# SparkFun_MicroMod_DA16200_Function.net
KiCad netlist of a schematic drawn in EAGLE
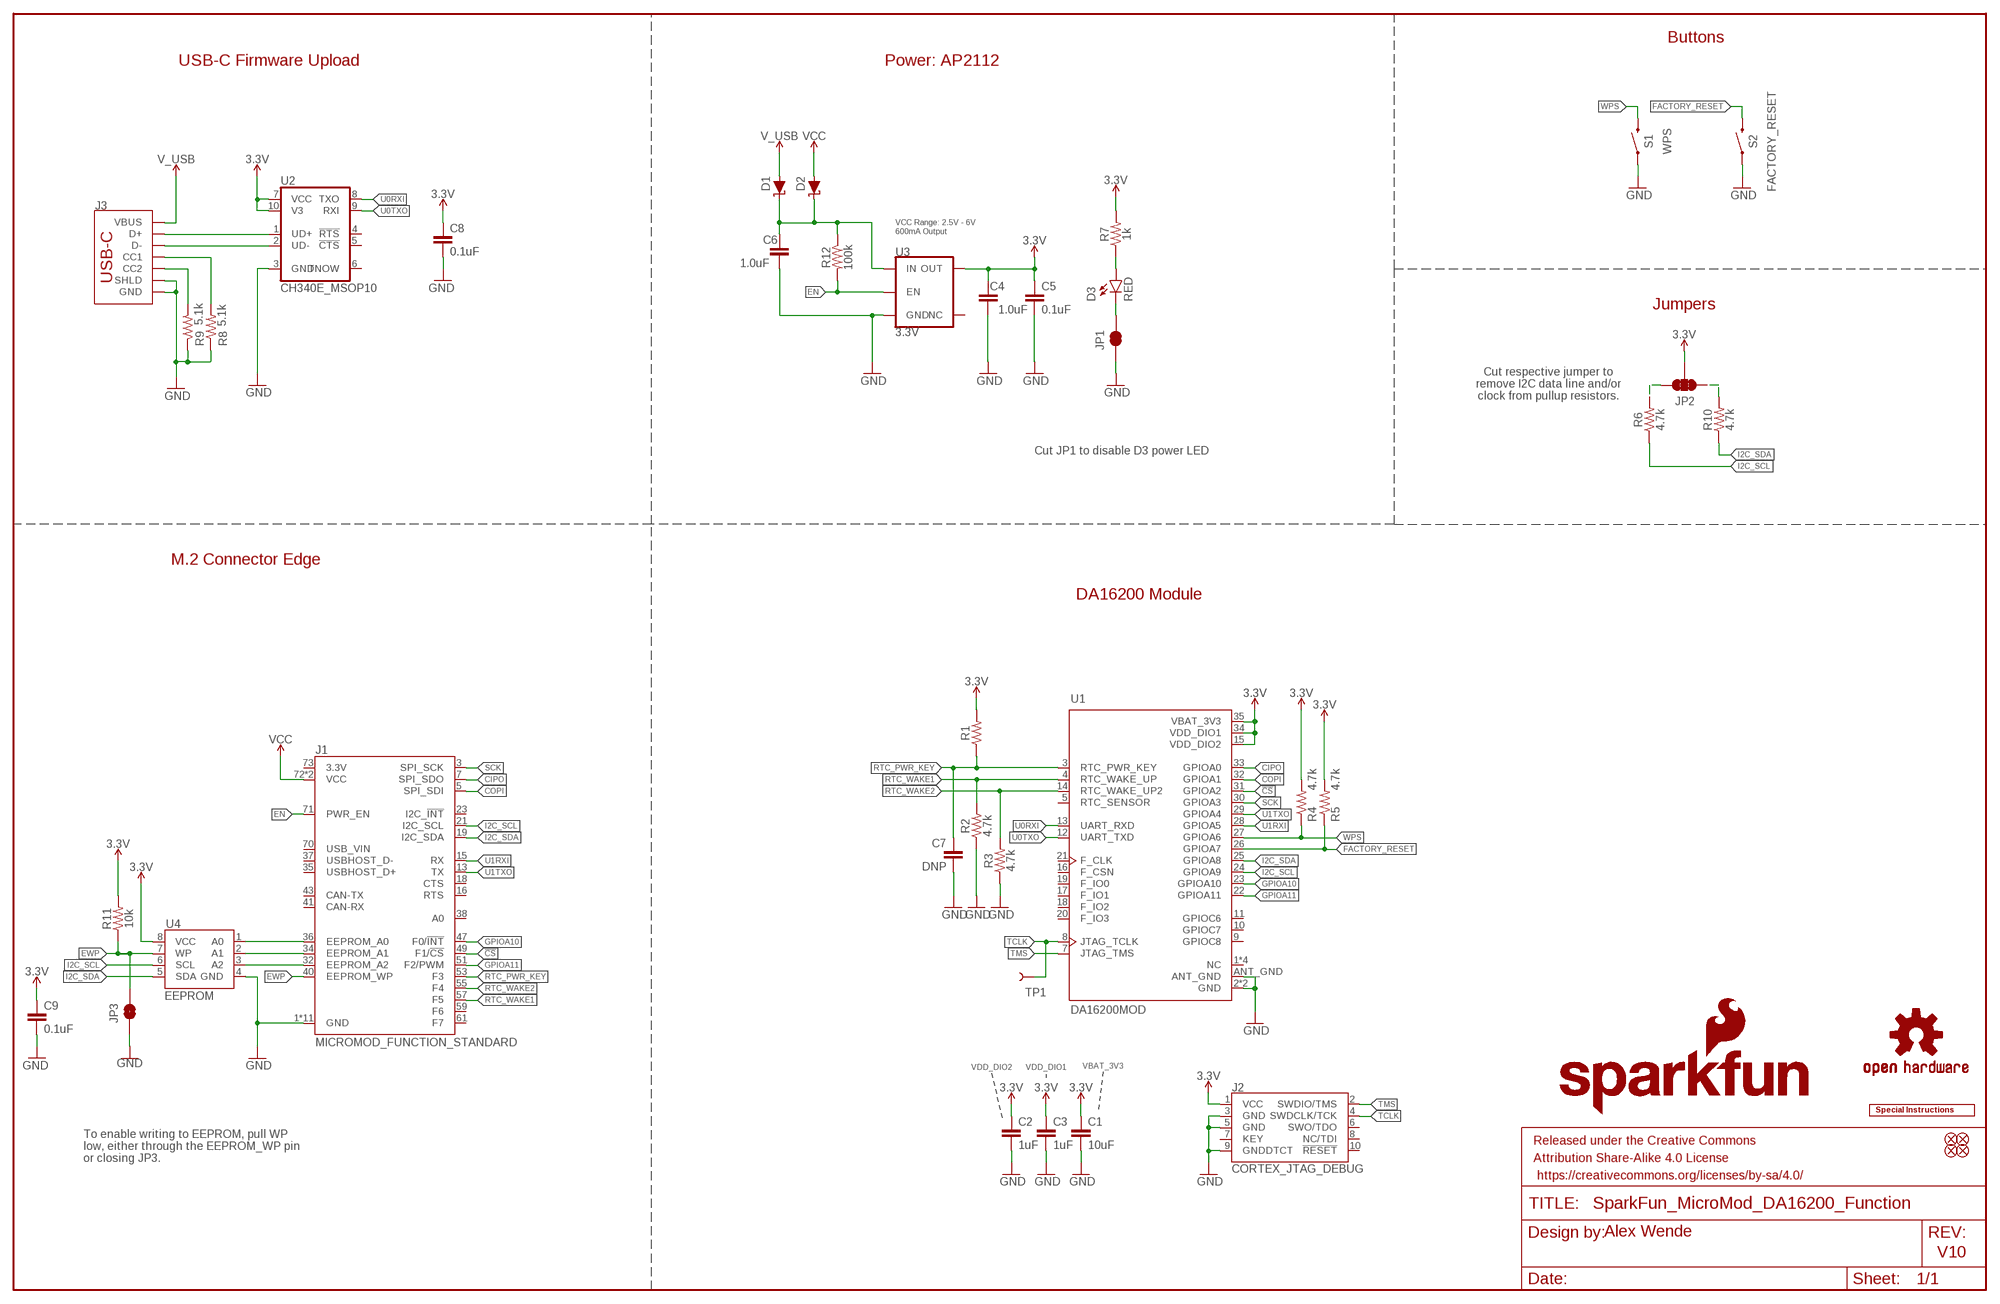
[diagram p0: schematic, sheet 1]

(export (version "E")
  (design (tool "Eeschema 10.0.6"))
  (components
    (comp (ref "C1")
      (value "10uF")
      (footprint "eagle-import:0603")
      (libsource (lib "eagle-import") (part "10UF-0603-6.3V-20%"))
    )
    (comp (ref "C2")
      (value "1uF")
      (footprint "eagle-import:0603")
      (libsource (lib "eagle-import") (part "1.0UF-0603-16V-10%"))
    )
    (comp (ref "C3")
      (value "1uF")
      (footprint "eagle-import:0603")
      (libsource (lib "eagle-import") (part "1.0UF-0603-16V-10%"))
    )
    (comp (ref "C4")
      (value "1.0uF")
      (footprint "eagle-import:0603")
      (libsource (lib "eagle-import") (part "1.0UF-0603-16V-10%"))
    )
    (comp (ref "C5")
      (value "0.1uF")
      (footprint "eagle-import:0603")
      (libsource (lib "eagle-import") (part "0.1UF-0603-25V-(+80/-20%)"))
    )
    (comp (ref "C6")
      (value "1.0uF")
      (footprint "eagle-import:0603")
      (libsource (lib "eagle-import") (part "1.0UF-0603-16V-10%"))
    )
    (comp (ref "C7")
      (value "DNP")
      (footprint "eagle-import:0603")
      (libsource (lib "eagle-import") (part "CAP-0603"))
    )
    (comp (ref "C8")
      (value "0.1uF")
      (footprint "eagle-import:0603")
      (libsource (lib "eagle-import") (part "0.1UF-0603-25V-(+80/-20%)"))
    )
    (comp (ref "C9")
      (value "0.1uF")
      (footprint "eagle-import:0603")
      (libsource (lib "eagle-import") (part "0.1UF-0603-25V-(+80/-20%)"))
    )
    (comp (ref "D1")
      (value "DIODE-SCHOTTKY-BAT60A")
      (footprint "eagle-import:SOD-323")
      (libsource (lib "eagle-import") (part "DIODE-SCHOTTKY-BAT60A"))
    )
    (comp (ref "D2")
      (value "DIODE-SCHOTTKY-BAT60A")
      (footprint "eagle-import:SOD-323")
      (libsource (lib "eagle-import") (part "DIODE-SCHOTTKY-BAT60A"))
    )
    (comp (ref "D3")
      (value "RED")
      (footprint "eagle-import:LED-0603")
      (libsource (lib "eagle-import") (part "LED-0603_RIGHT_ANGLE"))
    )
    (comp (ref "FD1")
      (value "FIDUCIAL1X2")
      (footprint "eagle-import:FIDUCIAL-1X2")
      (libsource (lib "eagle-import") (part "FIDUCIAL1X2"))
    )
    (comp (ref "FD2")
      (value "FIDUCIAL1X2")
      (footprint "eagle-import:FIDUCIAL-1X2")
      (libsource (lib "eagle-import") (part "FIDUCIAL1X2"))
    )
    (comp (ref "FD3")
      (value "FIDUCIAL1X2")
      (footprint "eagle-import:FIDUCIAL-1X2")
      (libsource (lib "eagle-import") (part "FIDUCIAL1X2"))
    )
    (comp (ref "FD4")
      (value "FIDUCIAL1X2")
      (footprint "eagle-import:FIDUCIAL-1X2")
      (libsource (lib "eagle-import") (part "FIDUCIAL1X2"))
    )
    (comp (ref "FRAME2")
      (value "FRAME-LEDGER")
      (footprint "eagle-import:CREATIVE_COMMONS")
      (libsource (lib "eagle-import") (part "FRAME-LEDGER"))
    )
    (comp (ref "J1")
      (value "MICROMOD_FUNCTION_STANDARD")
      (footprint "eagle-import:M.2-CARD-E-22_FUNCTION_STANDARD")
      (libsource (lib "eagle-import") (part "MICROMOD_FUNCTION_STANDARD"))
    )
    (comp (ref "J2")
      (value "CORTEX_JTAG_DEBUG")
      (footprint "eagle-import:2X5-PTH-1.27MM-NO_SILK")
      (libsource (lib "eagle-import") (part "CORTEX_JTAG_DEBUG_PTH_NS"))
    )
    (comp (ref "J3")
      (value "USB_C_2-LAYER_PADS")
      (footprint "eagle-import:USB-C-16P-2LAYER-PADS")
      (libsource (lib "eagle-import") (part "USB_C_2-LAYER_PADS"))
    )
    (comp (ref "JP1")
      (value "JUMPER-SMT_2_NC_TRACE_SILK")
      (footprint "eagle-import:SMT-JUMPER_2_NC_TRACE_SILK")
      (libsource (lib "eagle-import") (part "JUMPER-SMT_2_NC_TRACE_SILK"))
    )
    (comp (ref "JP2")
      (value "JUMPER-SMT_3_2-NC_TRACE_SILK")
      (footprint "eagle-import:SMT-JUMPER_3_2-NC_TRACE_SILK")
      (libsource (lib "eagle-import") (part "JUMPER-SMT_3_2-NC_TRACE_SILK"))
    )
    (comp (ref "JP3")
      (value "JUMPER-SMT_2_NO_SILK")
      (footprint "eagle-import:SMT-JUMPER_2_NO_SILK")
      (libsource (lib "eagle-import") (part "JUMPER-SMT_2_NO_SILK"))
    )
    (comp (ref "LOGO1")
      (value "SFE_LOGO_NAME_FLAME.2_INCH")
      (footprint "eagle-import:SFE_LOGO_NAME_FLAME_.2")
      (libsource (lib "eagle-import") (part "SFE_LOGO_NAME_FLAME.2_INCH"))
    )
    (comp (ref "LOGO2")
      (value "OSHW-LOGOS")
      (footprint "eagle-import:OSHW-LOGO-S")
      (libsource (lib "eagle-import") (part "OSHW-LOGOS"))
    )
    (comp (ref "LOGO3")
      (value "SPECIAL_INSTRUCTIONS-ORDERING")
      (footprint "eagle-import:ORDERING_INSTRUCTIONS")
      (libsource (lib "eagle-import") (part "SPECIAL_INSTRUCTIONS-ORDERING"))
    )
    (comp (ref "R1")
      (value "RESISTOR0603")
      (footprint "eagle-import:0603")
      (libsource (lib "eagle-import") (part "RESISTOR0603"))
    )
    (comp (ref "R2")
      (value "4.7k")
      (footprint "eagle-import:0603")
      (libsource (lib "eagle-import") (part "4.7KOHM-0603-1/10W-1%"))
    )
    (comp (ref "R3")
      (value "4.7k")
      (footprint "eagle-import:0603")
      (libsource (lib "eagle-import") (part "4.7KOHM-0603-1/10W-1%"))
    )
    (comp (ref "R4")
      (value "4.7k")
      (footprint "eagle-import:0603")
      (libsource (lib "eagle-import") (part "4.7KOHM-0603-1/10W-1%"))
    )
    (comp (ref "R5")
      (value "4.7k")
      (footprint "eagle-import:0603")
      (libsource (lib "eagle-import") (part "4.7KOHM-0603-1/10W-1%"))
    )
    (comp (ref "R6")
      (value "4.7k")
      (footprint "eagle-import:0603")
      (libsource (lib "eagle-import") (part "4.7KOHM-0603-1/10W-1%"))
    )
    (comp (ref "R7")
      (value "1k")
      (footprint "eagle-import:0402-TIGHT")
      (libsource (lib "eagle-import") (part "1KOHM-0402T-1/16W-1%"))
    )
    (comp (ref "R8")
      (value "5.1k")
      (footprint "eagle-import:0402-TIGHT")
      (libsource (lib "eagle-import") (part "5.1KOHM-0402T-1/16W-1%"))
    )
    (comp (ref "R9")
      (value "5.1k")
      (footprint "eagle-import:0402-TIGHT")
      (libsource (lib "eagle-import") (part "5.1KOHM-0402T-1/16W-1%"))
    )
    (comp (ref "R10")
      (value "4.7k")
      (footprint "eagle-import:0603")
      (libsource (lib "eagle-import") (part "4.7KOHM-0603-1/10W-1%"))
    )
    (comp (ref "R11")
      (value "10k")
      (footprint "eagle-import:0603")
      (libsource (lib "eagle-import") (part "10KOHM-0603-1/10W-1%"))
    )
    (comp (ref "R12")
      (value "100k")
      (footprint "eagle-import:0603")
      (libsource (lib "eagle-import") (part "100KOHM-0603-1/10W-1%"))
    )
    (comp (ref "S1")
      (value "WPS")
      (footprint "eagle-import:TACTILE_SWITCH_SMD_5.2MM")
      (libsource (lib "eagle-import") (part "MOMENTARY-SWITCH-SPST-SMD-5.2MM-TALL"))
    )
    (comp (ref "S2")
      (value "FACTORY_RESET")
      (footprint "eagle-import:TACTILE_SWITCH_SMD_5.2MM")
      (libsource (lib "eagle-import") (part "MOMENTARY-SWITCH-SPST-SMD-5.2MM-TALL"))
    )
    (comp (ref "TP1")
      (value "TEST-POINT3")
      (footprint "eagle-import:PAD.03X.03")
      (libsource (lib "eagle-import") (part "TEST-POINT3"))
    )
    (comp (ref "U1")
      (value "DA16200MOD")
      (footprint "eagle-import:XCVR_DA16200MOD-AAC4WA32")
      (libsource (lib "eagle-import") (part "DA16200MOD-AAC4WA32"))
    )
    (comp (ref "U2")
      (value "CH340E_MSOP10")
      (footprint "eagle-import:MSOP10")
      (libsource (lib "eagle-import") (part "CH340E_MSOP10"))
    )
    (comp (ref "U3")
      (value "3.3V")
      (footprint "eagle-import:SOT23-5")
      (libsource (lib "eagle-import") (part "V_REG_AP2112K-3.3V"))
    )
    (comp (ref "U4")
      (value "EEPROM")
      (footprint "eagle-import:SO08")
      (libsource (lib "eagle-import") (part "EEPROM-I2C512K"))
    )
  )
  (nets
    (net (code "1") (name "/~{CS}") (class "Default")
      (node (ref "J1") (pin "49") (pinfunction "F1/~{CS}_49") (pintype "bidirectional"))
      (node (ref "U1") (pin "31") (pinfunction "GPIOA2_31") (pintype "bidirectional"))
    )
    (net (code "2") (name "3.3V") (class "Default")
      (node (ref "C1") (pin "1") (pinfunction "1_1") (pintype "passive"))
      (node (ref "C2") (pin "1") (pinfunction "1_1") (pintype "passive"))
      (node (ref "C3") (pin "1") (pinfunction "1_1") (pintype "passive"))
      (node (ref "C4") (pin "1") (pinfunction "1_1") (pintype "passive"))
      (node (ref "C5") (pin "1") (pinfunction "1_1") (pintype "passive"))
      (node (ref "C8") (pin "1") (pinfunction "1_1") (pintype "passive"))
      (node (ref "C9") (pin "1") (pinfunction "1_1") (pintype "passive"))
      (node (ref "J2") (pin "1") (pinfunction "VCC_1") (pintype "bidirectional"))
      (node (ref "JP2") (pin "2") (pinfunction "2_2") (pintype "passive"))
      (node (ref "R1") (pin "2") (pinfunction "2_2") (pintype "passive"))
      (node (ref "R11") (pin "2") (pinfunction "2_2") (pintype "passive"))
      (node (ref "R4") (pin "2") (pinfunction "2_2") (pintype "passive"))
      (node (ref "R5") (pin "2") (pinfunction "2_2") (pintype "passive"))
      (node (ref "R7") (pin "2") (pinfunction "2_2") (pintype "passive"))
      (node (ref "U1") (pin "15") (pinfunction "VDD_DIO2_15") (pintype "power_in"))
      (node (ref "U1") (pin "34") (pinfunction "VDD_DIO1_34") (pintype "power_in"))
      (node (ref "U1") (pin "35") (pinfunction "VBAT_3V3_35") (pintype "power_in"))
      (node (ref "U2") (pin "10") (pinfunction "V3_10") (pintype "bidirectional"))
      (node (ref "U2") (pin "7") (pinfunction "VCC_7") (pintype "bidirectional"))
      (node (ref "U3") (pin "5") (pinfunction "OUT_5") (pintype "passive"))
      (node (ref "U4") (pin "8") (pinfunction "VCC_8") (pintype "power_in"))
    )
    (net (code "3") (name "CIPO") (class "Default")
      (node (ref "J1") (pin "7") (pinfunction "SPI_SDO_7") (pintype "bidirectional"))
      (node (ref "U1") (pin "33") (pinfunction "GPIOA0_33") (pintype "bidirectional"))
    )
    (net (code "4") (name "COPI") (class "Default")
      (node (ref "J1") (pin "5") (pinfunction "SPI_SDI_5") (pintype "bidirectional"))
      (node (ref "U1") (pin "32") (pinfunction "GPIOA1_32") (pintype "bidirectional"))
    )
    (net (code "5") (name "EN") (class "Default")
      (node (ref "J1") (pin "71") (pinfunction "PWR_EN_71") (pintype "bidirectional"))
      (node (ref "R12") (pin "2") (pinfunction "2_2") (pintype "passive"))
      (node (ref "U3") (pin "3") (pinfunction "EN_3") (pintype "input"))
    )
    (net (code "6") (name "EWP") (class "Default")
      (node (ref "J1") (pin "40") (pinfunction "EEPROM_WP_40") (pintype "bidirectional"))
      (node (ref "JP3") (pin "2") (pinfunction "2_2") (pintype "passive"))
      (node (ref "R11") (pin "1") (pinfunction "1_1") (pintype "passive"))
      (node (ref "U4") (pin "7") (pinfunction "WP_7") (pintype "bidirectional"))
    )
    (net (code "7") (name "FACTORY_RESET") (class "Default")
      (node (ref "R5") (pin "1") (pinfunction "1_1") (pintype "passive"))
      (node (ref "S2") (pin "3") (pinfunction "2_3") (pintype "passive"))
      (node (ref "U1") (pin "26") (pinfunction "GPIOA7_26") (pintype "bidirectional"))
    )
    (net (code "8") (name "GND") (class "Default")
      (node (ref "C1") (pin "2") (pinfunction "2_2") (pintype "passive"))
      (node (ref "C2") (pin "2") (pinfunction "2_2") (pintype "passive"))
      (node (ref "C3") (pin "2") (pinfunction "2_2") (pintype "passive"))
      (node (ref "C4") (pin "2") (pinfunction "2_2") (pintype "passive"))
      (node (ref "C5") (pin "2") (pinfunction "2_2") (pintype "passive"))
      (node (ref "C6") (pin "2") (pinfunction "2_2") (pintype "passive"))
      (node (ref "C7") (pin "2") (pinfunction "2_2") (pintype "passive"))
      (node (ref "C8") (pin "2") (pinfunction "2_2") (pintype "passive"))
      (node (ref "C9") (pin "2") (pinfunction "2_2") (pintype "passive"))
      (node (ref "J1") (pin "1") (pinfunction "GND_1") (pintype "bidirectional"))
      (node (ref "J1") (pin "33") (pinfunction "GND_33") (pintype "bidirectional"))
      (node (ref "J1") (pin "39") (pinfunction "GND_39") (pintype "bidirectional"))
      (node (ref "J1") (pin "45") (pinfunction "GND_45") (pintype "bidirectional"))
      (node (ref "J1") (pin "75") (pinfunction "GND_75") (pintype "bidirectional"))
      (node (ref "J1") (pin "GND1") (pinfunction "GND_GND1") (pintype "bidirectional"))
      (node (ref "J1") (pin "GND2") (pinfunction "GND_GND2") (pintype "bidirectional"))
      (node (ref "J1") (pin "GND3") (pinfunction "GND_GND3") (pintype "bidirectional"))
      (node (ref "J1") (pin "GND4") (pinfunction "GND_GND4") (pintype "bidirectional"))
      (node (ref "J1") (pin "GND5") (pinfunction "GND_GND5") (pintype "bidirectional"))
      (node (ref "J1") (pin "GND6") (pinfunction "GND_GND6") (pintype "bidirectional"))
      (node (ref "J2") (pin "3") (pinfunction "GND_3") (pintype "bidirectional"))
      (node (ref "J2") (pin "5") (pinfunction "GND_5") (pintype "bidirectional"))
      (node (ref "J2") (pin "9") (pinfunction "GNDDTCT_9") (pintype "bidirectional"))
      (node (ref "J3") (pin "GND") (pinfunction "GND_GND") (pintype "bidirectional"))
      (node (ref "J3") (pin "GND2") (pinfunction "GND_GND2") (pintype "bidirectional"))
      (node (ref "J3") (pin "SHLD1") (pinfunction "SHLD_SHLD1") (pintype "bidirectional"))
      (node (ref "J3") (pin "SHLD2") (pinfunction "SHLD_SHLD2") (pintype "bidirectional"))
      (node (ref "J3") (pin "SHLD3") (pinfunction "SHLD_SHLD3") (pintype "bidirectional"))
      (node (ref "J3") (pin "SHLD4") (pinfunction "SHLD_SHLD4") (pintype "bidirectional"))
      (node (ref "JP1") (pin "1") (pinfunction "1_1") (pintype "passive"))
      (node (ref "JP3") (pin "1") (pinfunction "1_1") (pintype "passive"))
      (node (ref "R2") (pin "1") (pinfunction "1_1") (pintype "passive"))
      (node (ref "R3") (pin "1") (pinfunction "1_1") (pintype "passive"))
      (node (ref "R8") (pin "1") (pinfunction "1_1") (pintype "passive"))
      (node (ref "R9") (pin "1") (pinfunction "1_1") (pintype "passive"))
      (node (ref "S1") (pin "1") (pinfunction "1_1") (pintype "passive"))
      (node (ref "S2") (pin "1") (pinfunction "1_1") (pintype "passive"))
      (node (ref "U1") (pin "2") (pinfunction "GND_2") (pintype "power_in"))
      (node (ref "U1") (pin "ANT_GND") (pinfunction "ANT_GND_ANT_GND") (pintype "power_in"))
      (node (ref "U1") (pin "GND") (pinfunction "GND_GND") (pintype "power_in"))
      (node (ref "U2") (pin "3") (pinfunction "GND_3") (pintype "bidirectional"))
      (node (ref "U3") (pin "2") (pinfunction "GND_2") (pintype "input"))
      (node (ref "U4") (pin "4") (pinfunction "GND_4") (pintype "power_in"))
    )
    (net (code "9") (name "GPIOA10") (class "Default")
      (node (ref "J1") (pin "47") (pinfunction "F0/~{INT}_47") (pintype "bidirectional"))
      (node (ref "U1") (pin "23") (pinfunction "GPIOA10_23") (pintype "bidirectional"))
    )
    (net (code "10") (name "GPIOA11") (class "Default")
      (node (ref "J1") (pin "51") (pinfunction "F2/PWM_51") (pintype "bidirectional"))
      (node (ref "U1") (pin "22") (pinfunction "GPIOA11_22") (pintype "bidirectional"))
    )
    (net (code "11") (name "I2C_SCL") (class "Default")
      (node (ref "J1") (pin "21") (pinfunction "I2C_SCL_21") (pintype "bidirectional"))
      (node (ref "R6") (pin "1") (pinfunction "1_1") (pintype "passive"))
      (node (ref "U1") (pin "24") (pinfunction "GPIOA9_24") (pintype "bidirectional"))
      (node (ref "U4") (pin "6") (pinfunction "SCL_6") (pintype "bidirectional"))
    )
    (net (code "12") (name "I2C_SDA") (class "Default")
      (node (ref "J1") (pin "19") (pinfunction "I2C_SDA_19") (pintype "bidirectional"))
      (node (ref "R10") (pin "1") (pinfunction "1_1") (pintype "passive"))
      (node (ref "U1") (pin "25") (pinfunction "GPIOA8_25") (pintype "bidirectional"))
      (node (ref "U4") (pin "5") (pinfunction "SDA_5") (pintype "bidirectional"))
    )
    (net (code "13") (name "Net-(D3-PadA)") (class "Default")
      (node (ref "D3") (pin "A") (pinfunction "A_A") (pintype "passive"))
      (node (ref "R7") (pin "1") (pinfunction "1_1") (pintype "passive"))
    )
    (net (code "14") (name "Net-(D3-PadC)") (class "Default")
      (node (ref "D3") (pin "C") (pinfunction "C_C") (pintype "passive"))
      (node (ref "JP1") (pin "2") (pinfunction "2_2") (pintype "passive"))
    )
    (net (code "15") (name "Net-(J1-EEPROM_A0)") (class "Default")
      (node (ref "J1") (pin "36") (pinfunction "EEPROM_A0_36") (pintype "bidirectional"))
      (node (ref "U4") (pin "1") (pinfunction "A0_1") (pintype "bidirectional"))
    )
    (net (code "16") (name "Net-(J1-EEPROM_A1)") (class "Default")
      (node (ref "J1") (pin "34") (pinfunction "EEPROM_A1_34") (pintype "bidirectional"))
      (node (ref "U4") (pin "2") (pinfunction "A1_2") (pintype "bidirectional"))
    )
    (net (code "17") (name "Net-(J1-EEPROM_A2)") (class "Default")
      (node (ref "J1") (pin "32") (pinfunction "EEPROM_A2_32") (pintype "bidirectional"))
      (node (ref "U4") (pin "3") (pinfunction "A2_3") (pintype "bidirectional"))
    )
    (net (code "18") (name "Net-(J3-CC1)") (class "Default")
      (node (ref "J3") (pin "A5") (pinfunction "CC1_A5") (pintype "bidirectional"))
      (node (ref "R8") (pin "2") (pinfunction "2_2") (pintype "passive"))
    )
    (net (code "19") (name "Net-(J3-CC2)") (class "Default")
      (node (ref "J3") (pin "B5") (pinfunction "CC2_B5") (pintype "bidirectional"))
      (node (ref "R9") (pin "2") (pinfunction "2_2") (pintype "passive"))
    )
    (net (code "20") (name "Net-(JP2-Pad1)") (class "Default")
      (node (ref "JP2") (pin "1") (pinfunction "1_1") (pintype "passive"))
      (node (ref "R10") (pin "2") (pinfunction "2_2") (pintype "passive"))
    )
    (net (code "21") (name "Net-(JP2-Pad3)") (class "Default")
      (node (ref "JP2") (pin "3") (pinfunction "3_3") (pintype "passive"))
      (node (ref "R6") (pin "2") (pinfunction "2_2") (pintype "passive"))
    )
    (net (code "22") (name "Net-(U2-UD+)") (class "Default")
      (node (ref "J3") (pin "A6") (pinfunction "D+_A6") (pintype "bidirectional"))
      (node (ref "J3") (pin "B6") (pinfunction "D+_B6") (pintype "bidirectional"))
      (node (ref "U2") (pin "1") (pinfunction "UD+_1") (pintype "bidirectional"))
    )
    (net (code "23") (name "Net-(U2-UD-)") (class "Default")
      (node (ref "J3") (pin "A7") (pinfunction "D-_A7") (pintype "bidirectional"))
      (node (ref "J3") (pin "B7") (pinfunction "D-_B7") (pintype "bidirectional"))
      (node (ref "U2") (pin "2") (pinfunction "UD-_2") (pintype "bidirectional"))
    )
    (net (code "24") (name "Net-(U3-IN)") (class "Default")
      (node (ref "C6") (pin "1") (pinfunction "1_1") (pintype "passive"))
      (node (ref "D1") (pin "C") (pinfunction "C_C") (pintype "passive"))
      (node (ref "D2") (pin "C") (pinfunction "C_C") (pintype "passive"))
      (node (ref "R12") (pin "1") (pinfunction "1_1") (pintype "passive"))
      (node (ref "U3") (pin "1") (pinfunction "IN_1") (pintype "input"))
    )
    (net (code "25") (name "RTC_PWR_KEY") (class "Default")
      (node (ref "C7") (pin "1") (pinfunction "1_1") (pintype "passive"))
      (node (ref "J1") (pin "53") (pinfunction "F3_53") (pintype "bidirectional"))
      (node (ref "R1") (pin "1") (pinfunction "1_1") (pintype "passive"))
      (node (ref "U1") (pin "3") (pinfunction "RTC_PWR_KEY_3") (pintype "input"))
    )
    (net (code "26") (name "RTC_WAKE1") (class "Default")
      (node (ref "J1") (pin "57") (pinfunction "F5_57") (pintype "bidirectional"))
      (node (ref "R2") (pin "2") (pinfunction "2_2") (pintype "passive"))
      (node (ref "U1") (pin "4") (pinfunction "RTC_WAKE_UP_4") (pintype "input"))
    )
    (net (code "27") (name "RTC_WAKE2") (class "Default")
      (node (ref "J1") (pin "55") (pinfunction "F4_55") (pintype "bidirectional"))
      (node (ref "R3") (pin "2") (pinfunction "2_2") (pintype "passive"))
      (node (ref "U1") (pin "14") (pinfunction "RTC_WAKE_UP2_14") (pintype "input"))
    )
    (net (code "28") (name "SCK") (class "Default")
      (node (ref "J1") (pin "3") (pinfunction "SPI_SCK_3") (pintype "bidirectional"))
      (node (ref "U1") (pin "30") (pinfunction "GPIOA3_30") (pintype "bidirectional"))
    )
    (net (code "29") (name "TCLK") (class "Default")
      (node (ref "J2") (pin "4") (pinfunction "SWDCLK/TCK_4") (pintype "bidirectional"))
      (node (ref "TP1") (pin "1") (pinfunction "1_1") (pintype "bidirectional"))
      (node (ref "U1") (pin "8") (pinfunction "JTAG_TCLK_8") (pintype "bidirectional"))
    )
    (net (code "30") (name "TMS") (class "Default")
      (node (ref "J2") (pin "2") (pinfunction "SWDIO/TMS_2") (pintype "bidirectional"))
      (node (ref "U1") (pin "7") (pinfunction "JTAG_TMS_7") (pintype "bidirectional"))
    )
    (net (code "31") (name "U0RXI") (class "Default")
      (node (ref "U1") (pin "13") (pinfunction "UART_RXD_13") (pintype "input"))
      (node (ref "U2") (pin "8") (pinfunction "TXO_8") (pintype "bidirectional"))
    )
    (net (code "32") (name "U0TXO") (class "Default")
      (node (ref "U1") (pin "12") (pinfunction "UART_TXD_12") (pintype "output"))
      (node (ref "U2") (pin "9") (pinfunction "RXI_9") (pintype "bidirectional"))
    )
    (net (code "33") (name "U1RXI") (class "Default")
      (node (ref "J1") (pin "15") (pinfunction "RX_15") (pintype "bidirectional"))
      (node (ref "U1") (pin "28") (pinfunction "GPIOA5_28") (pintype "bidirectional"))
    )
    (net (code "34") (name "U1TXO") (class "Default")
      (node (ref "J1") (pin "13") (pinfunction "TX_13") (pintype "bidirectional"))
      (node (ref "U1") (pin "29") (pinfunction "GPIOA4_29") (pintype "bidirectional"))
    )
    (net (code "35") (name "VCC") (class "Default")
      (node (ref "D2") (pin "A") (pinfunction "A_A") (pintype "passive"))
      (node (ref "J1") (pin "72") (pinfunction "VCC_72") (pintype "bidirectional"))
      (node (ref "J1") (pin "74") (pinfunction "VCC_74") (pintype "bidirectional"))
    )
    (net (code "36") (name "V_USB") (class "Default")
      (node (ref "D1") (pin "A") (pinfunction "A_A") (pintype "passive"))
      (node (ref "J3") (pin "VBUS1") (pinfunction "VBUS_VBUS1") (pintype "bidirectional"))
      (node (ref "J3") (pin "VBUS2") (pinfunction "VBUS_VBUS2") (pintype "bidirectional"))
    )
    (net (code "37") (name "WPS") (class "Default")
      (node (ref "R4") (pin "1") (pinfunction "1_1") (pintype "passive"))
      (node (ref "S1") (pin "3") (pinfunction "2_3") (pintype "passive"))
      (node (ref "U1") (pin "27") (pinfunction "GPIOA6_27") (pintype "bidirectional"))
    )
    (net (code "38") (name "unconnected-(J1-3.3V-Pad73)") (class "Default")
      (node (ref "J1") (pin "73") (pinfunction "3.3V_73") (pintype "bidirectional"))
    )
    (net (code "39") (name "unconnected-(J1-A0-Pad38)") (class "Default")
      (node (ref "J1") (pin "38") (pinfunction "A0_38") (pintype "bidirectional"))
    )
    (net (code "40") (name "unconnected-(J1-CAN-RX-Pad41)") (class "Default")
      (node (ref "J1") (pin "41") (pinfunction "CAN-RX_41") (pintype "bidirectional"))
    )
    (net (code "41") (name "unconnected-(J1-CAN-TX-Pad43)") (class "Default")
      (node (ref "J1") (pin "43") (pinfunction "CAN-TX_43") (pintype "bidirectional"))
    )
    (net (code "42") (name "unconnected-(J1-CTS-Pad18)") (class "Default")
      (node (ref "J1") (pin "18") (pinfunction "CTS_18") (pintype "bidirectional"))
    )
    (net (code "43") (name "unconnected-(J1-F6-Pad59)") (class "Default")
      (node (ref "J1") (pin "59") (pinfunction "F6_59") (pintype "bidirectional"))
    )
    (net (code "44") (name "unconnected-(J1-F7-Pad61)") (class "Default")
      (node (ref "J1") (pin "61") (pinfunction "F7_61") (pintype "bidirectional"))
    )
    (net (code "45") (name "unconnected-(J1-I2C_~{INT}-Pad23)") (class "Default")
      (node (ref "J1") (pin "23") (pinfunction "I2C_~{INT}_23") (pintype "bidirectional"))
    )
    (net (code "46") (name "unconnected-(J1-RTS-Pad16)") (class "Default")
      (node (ref "J1") (pin "16") (pinfunction "RTS_16") (pintype "bidirectional"))
    )
    (net (code "47") (name "unconnected-(J1-USBHOST_D+-Pad35)") (class "Default")
      (node (ref "J1") (pin "35") (pinfunction "USBHOST_D+_35") (pintype "bidirectional"))
    )
    (net (code "48") (name "unconnected-(J1-USBHOST_D--Pad37)") (class "Default")
      (node (ref "J1") (pin "37") (pinfunction "USBHOST_D-_37") (pintype "bidirectional"))
    )
    (net (code "49") (name "unconnected-(J1-USB_VIN-Pad70)") (class "Default")
      (node (ref "J1") (pin "70") (pinfunction "USB_VIN_70") (pintype "bidirectional"))
    )
    (net (code "50") (name "unconnected-(J2-KEY-Pad7)") (class "Default")
      (node (ref "J2") (pin "7") (pinfunction "KEY_7") (pintype "bidirectional"))
    )
    (net (code "51") (name "unconnected-(J2-NC{slash}TDI-Pad8)") (class "Default")
      (node (ref "J2") (pin "8") (pinfunction "NC/TDI_8") (pintype "bidirectional"))
    )
    (net (code "52") (name "unconnected-(J2-SWO{slash}TDO-Pad6)") (class "Default")
      (node (ref "J2") (pin "6") (pinfunction "SWO/TDO_6") (pintype "bidirectional"))
    )
    (net (code "53") (name "unconnected-(J2-~{RESET}-Pad10)") (class "Default")
      (node (ref "J2") (pin "10") (pinfunction "~{RESET}_10") (pintype "bidirectional"))
    )
    (net (code "54") (name "unconnected-(U1-F_CLK-Pad21)") (class "Default")
      (node (ref "U1") (pin "21") (pinfunction "F_CLK_21") (pintype "bidirectional"))
    )
    (net (code "55") (name "unconnected-(U1-F_CSN-Pad16)") (class "Default")
      (node (ref "U1") (pin "16") (pinfunction "F_CSN_16") (pintype "bidirectional"))
    )
    (net (code "56") (name "unconnected-(U1-F_IO0-Pad19)") (class "Default")
      (node (ref "U1") (pin "19") (pinfunction "F_IO0_19") (pintype "bidirectional"))
    )
    (net (code "57") (name "unconnected-(U1-F_IO1-Pad17)") (class "Default")
      (node (ref "U1") (pin "17") (pinfunction "F_IO1_17") (pintype "bidirectional"))
    )
    (net (code "58") (name "unconnected-(U1-F_IO2-Pad18)") (class "Default")
      (node (ref "U1") (pin "18") (pinfunction "F_IO2_18") (pintype "bidirectional"))
    )
    (net (code "59") (name "unconnected-(U1-F_IO3-Pad20)") (class "Default")
      (node (ref "U1") (pin "20") (pinfunction "F_IO3_20") (pintype "bidirectional"))
    )
    (net (code "60") (name "unconnected-(U1-GPIOC6-Pad11)") (class "Default")
      (node (ref "U1") (pin "11") (pinfunction "GPIOC6_11") (pintype "bidirectional"))
    )
    (net (code "61") (name "unconnected-(U1-GPIOC7-Pad10)") (class "Default")
      (node (ref "U1") (pin "10") (pinfunction "GPIOC7_10") (pintype "bidirectional"))
    )
    (net (code "62") (name "unconnected-(U1-GPIOC8-Pad9)") (class "Default")
      (node (ref "U1") (pin "9") (pinfunction "GPIOC8_9") (pintype "bidirectional"))
    )
    (net (code "63") (name "unconnected-(U1-NC-Pad1)") (class "Default")
      (node (ref "U1") (pin "1") (pinfunction "NC_1") (pintype "no_connect"))
    )
    (net (code "64") (name "unconnected-(U1-NC-Pad6)") (class "Default")
      (node (ref "U1") (pin "6") (pinfunction "NC_6") (pintype "no_connect"))
    )
    (net (code "65") (name "unconnected-(U1-NC-Pad36)") (class "Default")
      (node (ref "U1") (pin "36") (pinfunction "NC_36") (pintype "no_connect"))
    )
    (net (code "66") (name "unconnected-(U1-NC-Pad37)") (class "Default")
      (node (ref "U1") (pin "37") (pinfunction "NC_37") (pintype "no_connect"))
    )
    (net (code "67") (name "unconnected-(U1-RTC_SENSOR-Pad5)") (class "Default")
      (node (ref "U1") (pin "5") (pinfunction "RTC_SENSOR_5") (pintype "output"))
    )
    (net (code "68") (name "unconnected-(U2-TNOW-Pad6)") (class "Default")
      (node (ref "U2") (pin "6") (pinfunction "TNOW_6") (pintype "bidirectional"))
    )
    (net (code "69") (name "unconnected-(U2-~{CTS}-Pad5)") (class "Default")
      (node (ref "U2") (pin "5") (pinfunction "~{CTS}_5") (pintype "bidirectional"))
    )
    (net (code "70") (name "unconnected-(U2-~{RTS}-Pad4)") (class "Default")
      (node (ref "U2") (pin "4") (pinfunction "~{RTS}_4") (pintype "bidirectional"))
    )
    (net (code "71") (name "unconnected-(U3-NC-Pad4)") (class "Default")
      (node (ref "U3") (pin "4") (pinfunction "NC_4") (pintype "no_connect"))
    )
  )
)
